# remote.net
KiCad netlist of a schematic drawn in EAGLE
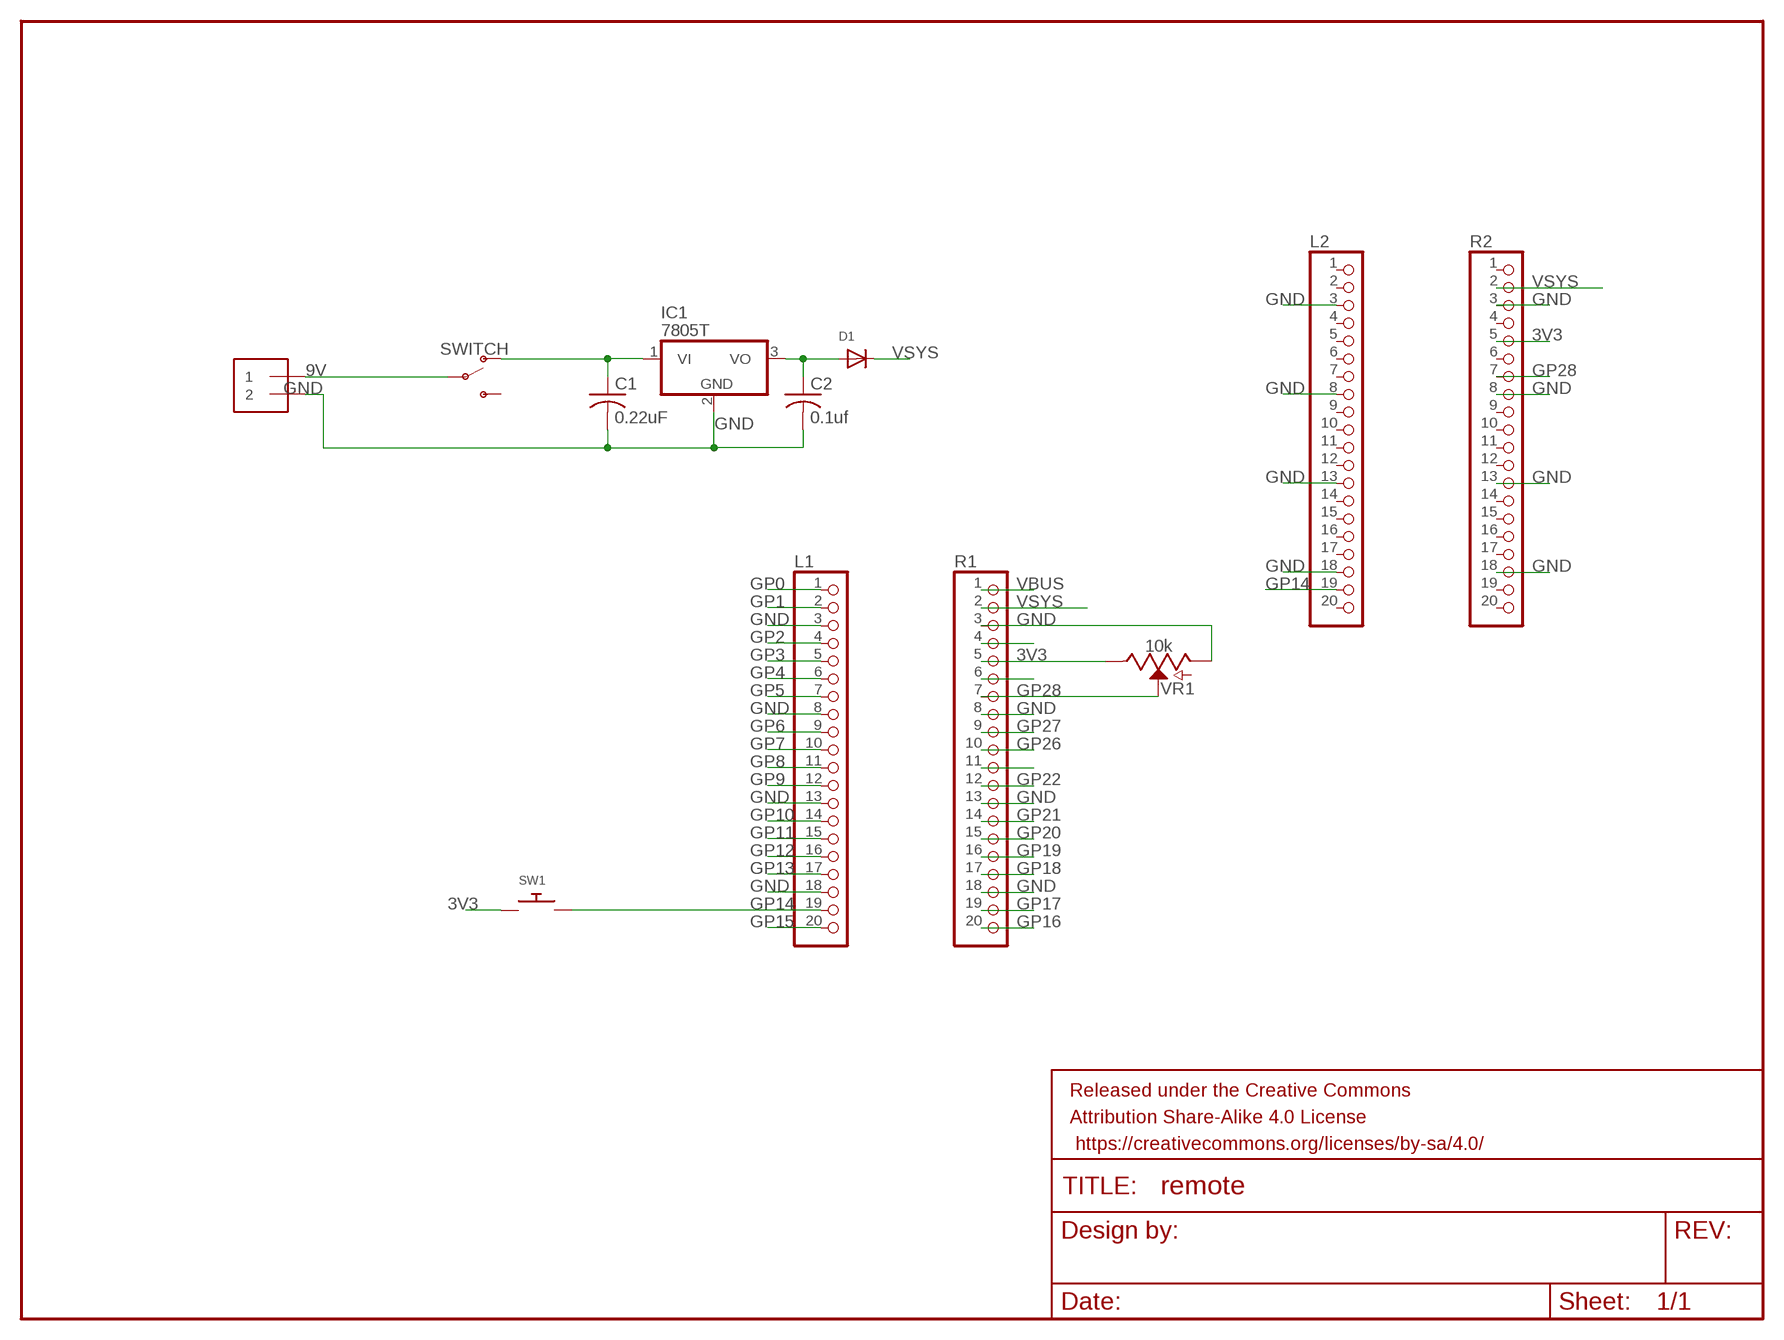
[diagram p0: schematic, sheet 1]

(export (version "E")
  (design (tool "Eeschema 10.0.6"))
  (components
    (comp (ref "9VBAT")
      (value "1X2-3.5MM")
      (footprint "eagle-import:1X2-3.5MM")
      (libsource (lib "eagle-import") (part "1X2-3.5MM"))
    )
    (comp (ref "C1")
      (value "0.22uF")
      (footprint "eagle-import:C050-025X075")
      (libsource (lib "eagle-import") (part "C-US050-025X075"))
    )
    (comp (ref "C2")
      (value "0.1uf")
      (footprint "eagle-import:C050-025X075")
      (libsource (lib "eagle-import") (part "C-US050-025X075"))
    )
    (comp (ref "D1")
      (value "DIODEDO-1N4148")
      (footprint "eagle-import:DO-1N4148")
      (libsource (lib "eagle-import") (part "DIODEDO-1N4148"))
    )
    (comp (ref "FRAME1")
      (value "FRAME-LETTER")
      (footprint "eagle-import:CREATIVE_COMMONS")
      (libsource (lib "eagle-import") (part "FRAME-LETTER"))
    )
    (comp (ref "IC1")
      (value "7805T")
      (footprint "eagle-import:TO220H")
      (libsource (lib "eagle-import") (part "78T05"))
    )
    (comp (ref "L1")
      (value "PINHD-1X20")
      (footprint "eagle-import:1X20")
      (libsource (lib "eagle-import") (part "PINHD-1X20"))
    )
    (comp (ref "L2")
      (value "PINHD-1X20")
      (footprint "eagle-import:1X20")
      (libsource (lib "eagle-import") (part "PINHD-1X20"))
    )
    (comp (ref "R1")
      (value "PINHD-1X20")
      (footprint "eagle-import:1X20")
      (libsource (lib "eagle-import") (part "PINHD-1X20"))
    )
    (comp (ref "R2")
      (value "PINHD-1X20")
      (footprint "eagle-import:1X20")
      (libsource (lib "eagle-import") (part "PINHD-1X20"))
    )
    (comp (ref "SW1")
      (value "SWITCH_PUSHBUTTONEVQ-PE")
      (footprint "eagle-import:TACT_PANA-EVQ")
      (libsource (lib "eagle-import") (part "SWITCH_PUSHBUTTONEVQ-PE"))
    )
    (comp (ref "SWITCH")
      (value "SWITCH-SPDT-PTH-11.6X4.0MM-LOCK")
      (footprint "eagle-import:SWITCH_SPDT_PTH_11.6X4.0MM_LOCK")
      (libsource (lib "eagle-import") (part "SWITCH-SPDT-PTH-11.6X4.0MM-LOCK"))
    )
    (comp (ref "VR1")
      (value "10k")
      (footprint "eagle-import:POT-PTH-ALPS")
      (libsource (lib "eagle-import") (part "POTENTIOMETER-PTH-9MM-1/20W-20%"))
    )
  )
  (nets
    (net (code "1") (name "/3V3") (class "Default")
      (node (ref "R1") (pin "5") (pinfunction "5_5") (pintype "passive"))
      (node (ref "R2") (pin "5") (pinfunction "5_5") (pintype "passive"))
      (node (ref "SW1") (pin "P$1") (pinfunction "P$1_P$1") (pintype "passive"))
      (node (ref "VR1") (pin "P$1") (pinfunction "E_P$1") (pintype "passive"))
    )
    (net (code "2") (name "/9V") (class "Default")
      (node (ref "9VBAT") (pin "1") (pinfunction "1_1") (pintype "passive"))
      (node (ref "SWITCH") (pin "2") (pinfunction "P_2") (pintype "passive"))
    )
    (net (code "3") (name "/GND") (class "Default")
      (node (ref "9VBAT") (pin "2") (pinfunction "2_2") (pintype "passive"))
      (node (ref "C1") (pin "2") (pinfunction "2_2") (pintype "passive"))
      (node (ref "C2") (pin "2") (pinfunction "2_2") (pintype "passive"))
      (node (ref "IC1") (pin "2") (pinfunction "GND_2") (pintype "passive"))
      (node (ref "L1") (pin "13") (pinfunction "13_13") (pintype "passive"))
      (node (ref "L1") (pin "18") (pinfunction "18_18") (pintype "passive"))
      (node (ref "L1") (pin "3") (pinfunction "3_3") (pintype "passive"))
      (node (ref "L1") (pin "8") (pinfunction "8_8") (pintype "passive"))
      (node (ref "L2") (pin "13") (pinfunction "13_13") (pintype "passive"))
      (node (ref "L2") (pin "18") (pinfunction "18_18") (pintype "passive"))
      (node (ref "L2") (pin "3") (pinfunction "3_3") (pintype "passive"))
      (node (ref "L2") (pin "8") (pinfunction "8_8") (pintype "passive"))
      (node (ref "R1") (pin "13") (pinfunction "13_13") (pintype "passive"))
      (node (ref "R1") (pin "18") (pinfunction "18_18") (pintype "passive"))
      (node (ref "R1") (pin "3") (pinfunction "3_3") (pintype "passive"))
      (node (ref "R1") (pin "8") (pinfunction "8_8") (pintype "passive"))
      (node (ref "R2") (pin "13") (pinfunction "13_13") (pintype "passive"))
      (node (ref "R2") (pin "18") (pinfunction "18_18") (pintype "passive"))
      (node (ref "R2") (pin "3") (pinfunction "3_3") (pintype "passive"))
      (node (ref "R2") (pin "8") (pinfunction "8_8") (pintype "passive"))
      (node (ref "VR1") (pin "P$3") (pinfunction "A_P$3") (pintype "passive"))
    )
    (net (code "4") (name "/GP0") (class "Default")
      (node (ref "L1") (pin "1") (pinfunction "1_1") (pintype "passive"))
    )
    (net (code "5") (name "/GP1") (class "Default")
      (node (ref "L1") (pin "2") (pinfunction "2_2") (pintype "passive"))
    )
    (net (code "6") (name "/GP2") (class "Default")
      (node (ref "L1") (pin "4") (pinfunction "4_4") (pintype "passive"))
    )
    (net (code "7") (name "/GP3") (class "Default")
      (node (ref "L1") (pin "5") (pinfunction "5_5") (pintype "passive"))
    )
    (net (code "8") (name "/GP4") (class "Default")
      (node (ref "L1") (pin "6") (pinfunction "6_6") (pintype "passive"))
    )
    (net (code "9") (name "/GP5") (class "Default")
      (node (ref "L1") (pin "7") (pinfunction "7_7") (pintype "passive"))
    )
    (net (code "10") (name "/GP6") (class "Default")
      (node (ref "L1") (pin "9") (pinfunction "9_9") (pintype "passive"))
    )
    (net (code "11") (name "/GP7") (class "Default")
      (node (ref "L1") (pin "10") (pinfunction "10_10") (pintype "passive"))
    )
    (net (code "12") (name "/GP8") (class "Default")
      (node (ref "L1") (pin "11") (pinfunction "11_11") (pintype "passive"))
    )
    (net (code "13") (name "/GP9") (class "Default")
      (node (ref "L1") (pin "12") (pinfunction "12_12") (pintype "passive"))
    )
    (net (code "14") (name "/GP10") (class "Default")
      (node (ref "L1") (pin "14") (pinfunction "14_14") (pintype "passive"))
    )
    (net (code "15") (name "/GP11") (class "Default")
      (node (ref "L1") (pin "15") (pinfunction "15_15") (pintype "passive"))
    )
    (net (code "16") (name "/GP12") (class "Default")
      (node (ref "L1") (pin "16") (pinfunction "16_16") (pintype "passive"))
    )
    (net (code "17") (name "/GP13") (class "Default")
      (node (ref "L1") (pin "17") (pinfunction "17_17") (pintype "passive"))
    )
    (net (code "18") (name "/GP14") (class "Default")
      (node (ref "L1") (pin "19") (pinfunction "19_19") (pintype "passive"))
      (node (ref "L2") (pin "19") (pinfunction "19_19") (pintype "passive"))
      (node (ref "SW1") (pin "P$2") (pinfunction "P$2_P$2") (pintype "passive"))
    )
    (net (code "19") (name "/GP15") (class "Default")
      (node (ref "L1") (pin "20") (pinfunction "20_20") (pintype "passive"))
    )
    (net (code "20") (name "/GP16") (class "Default")
      (node (ref "R1") (pin "20") (pinfunction "20_20") (pintype "passive"))
    )
    (net (code "21") (name "/GP17") (class "Default")
      (node (ref "R1") (pin "19") (pinfunction "19_19") (pintype "passive"))
    )
    (net (code "22") (name "/GP18") (class "Default")
      (node (ref "R1") (pin "17") (pinfunction "17_17") (pintype "passive"))
    )
    (net (code "23") (name "/GP19") (class "Default")
      (node (ref "R1") (pin "16") (pinfunction "16_16") (pintype "passive"))
    )
    (net (code "24") (name "/GP20") (class "Default")
      (node (ref "R1") (pin "15") (pinfunction "15_15") (pintype "passive"))
    )
    (net (code "25") (name "/GP21") (class "Default")
      (node (ref "R1") (pin "14") (pinfunction "14_14") (pintype "passive"))
    )
    (net (code "26") (name "/GP22") (class "Default")
      (node (ref "R1") (pin "12") (pinfunction "12_12") (pintype "passive"))
    )
    (net (code "27") (name "/GP26") (class "Default")
      (node (ref "R1") (pin "10") (pinfunction "10_10") (pintype "passive"))
    )
    (net (code "28") (name "/GP27") (class "Default")
      (node (ref "R1") (pin "9") (pinfunction "9_9") (pintype "passive"))
    )
    (net (code "29") (name "/GP28") (class "Default")
      (node (ref "R1") (pin "7") (pinfunction "7_7") (pintype "passive"))
      (node (ref "R2") (pin "7") (pinfunction "7_7") (pintype "passive"))
      (node (ref "VR1") (pin "P$2") (pinfunction "S_P$2") (pintype "passive"))
    )
    (net (code "30") (name "/VBUS") (class "Default")
      (node (ref "R1") (pin "1") (pinfunction "1_1") (pintype "passive"))
    )
    (net (code "31") (name "/VSYS") (class "Default")
      (node (ref "D1") (pin "C") (pinfunction "C_C") (pintype "passive"))
      (node (ref "R1") (pin "2") (pinfunction "2_2") (pintype "passive"))
      (node (ref "R2") (pin "2") (pinfunction "2_2") (pintype "passive"))
    )
    (net (code "32") (name "Net-(IC1-VI)") (class "Default")
      (node (ref "C1") (pin "1") (pinfunction "1_1") (pintype "passive"))
      (node (ref "IC1") (pin "1") (pinfunction "VI_1") (pintype "input"))
      (node (ref "SWITCH") (pin "1") (pinfunction "O_1") (pintype "passive"))
    )
    (net (code "33") (name "Net-(IC1-VO)") (class "Default")
      (node (ref "C2") (pin "1") (pinfunction "1_1") (pintype "passive"))
      (node (ref "D1") (pin "A") (pinfunction "A_A") (pintype "passive"))
      (node (ref "IC1") (pin "3") (pinfunction "VO_3") (pintype "passive"))
    )
    (net (code "34") (name "unconnected-(L2-Pad1)") (class "Default")
      (node (ref "L2") (pin "1") (pinfunction "1_1") (pintype "passive"))
    )
    (net (code "35") (name "unconnected-(L2-Pad2)") (class "Default")
      (node (ref "L2") (pin "2") (pinfunction "2_2") (pintype "passive"))
    )
    (net (code "36") (name "unconnected-(L2-Pad4)") (class "Default")
      (node (ref "L2") (pin "4") (pinfunction "4_4") (pintype "passive"))
    )
    (net (code "37") (name "unconnected-(L2-Pad5)") (class "Default")
      (node (ref "L2") (pin "5") (pinfunction "5_5") (pintype "passive"))
    )
    (net (code "38") (name "unconnected-(L2-Pad6)") (class "Default")
      (node (ref "L2") (pin "6") (pinfunction "6_6") (pintype "passive"))
    )
    (net (code "39") (name "unconnected-(L2-Pad7)") (class "Default")
      (node (ref "L2") (pin "7") (pinfunction "7_7") (pintype "passive"))
    )
    (net (code "40") (name "unconnected-(L2-Pad9)") (class "Default")
      (node (ref "L2") (pin "9") (pinfunction "9_9") (pintype "passive"))
    )
    (net (code "41") (name "unconnected-(L2-Pad10)") (class "Default")
      (node (ref "L2") (pin "10") (pinfunction "10_10") (pintype "passive"))
    )
    (net (code "42") (name "unconnected-(L2-Pad11)") (class "Default")
      (node (ref "L2") (pin "11") (pinfunction "11_11") (pintype "passive"))
    )
    (net (code "43") (name "unconnected-(L2-Pad12)") (class "Default")
      (node (ref "L2") (pin "12") (pinfunction "12_12") (pintype "passive"))
    )
    (net (code "44") (name "unconnected-(L2-Pad14)") (class "Default")
      (node (ref "L2") (pin "14") (pinfunction "14_14") (pintype "passive"))
    )
    (net (code "45") (name "unconnected-(L2-Pad15)") (class "Default")
      (node (ref "L2") (pin "15") (pinfunction "15_15") (pintype "passive"))
    )
    (net (code "46") (name "unconnected-(L2-Pad16)") (class "Default")
      (node (ref "L2") (pin "16") (pinfunction "16_16") (pintype "passive"))
    )
    (net (code "47") (name "unconnected-(L2-Pad17)") (class "Default")
      (node (ref "L2") (pin "17") (pinfunction "17_17") (pintype "passive"))
    )
    (net (code "48") (name "unconnected-(L2-Pad20)") (class "Default")
      (node (ref "L2") (pin "20") (pinfunction "20_20") (pintype "passive"))
    )
    (net (code "49") (name "unconnected-(R1-Pad4)") (class "Default")
      (node (ref "R1") (pin "4") (pinfunction "4_4") (pintype "passive"))
    )
    (net (code "50") (name "unconnected-(R1-Pad6)") (class "Default")
      (node (ref "R1") (pin "6") (pinfunction "6_6") (pintype "passive"))
    )
    (net (code "51") (name "unconnected-(R1-Pad11)") (class "Default")
      (node (ref "R1") (pin "11") (pinfunction "11_11") (pintype "passive"))
    )
    (net (code "52") (name "unconnected-(R2-Pad1)") (class "Default")
      (node (ref "R2") (pin "1") (pinfunction "1_1") (pintype "passive"))
    )
    (net (code "53") (name "unconnected-(R2-Pad4)") (class "Default")
      (node (ref "R2") (pin "4") (pinfunction "4_4") (pintype "passive"))
    )
    (net (code "54") (name "unconnected-(R2-Pad6)") (class "Default")
      (node (ref "R2") (pin "6") (pinfunction "6_6") (pintype "passive"))
    )
    (net (code "55") (name "unconnected-(R2-Pad9)") (class "Default")
      (node (ref "R2") (pin "9") (pinfunction "9_9") (pintype "passive"))
    )
    (net (code "56") (name "unconnected-(R2-Pad10)") (class "Default")
      (node (ref "R2") (pin "10") (pinfunction "10_10") (pintype "passive"))
    )
    (net (code "57") (name "unconnected-(R2-Pad11)") (class "Default")
      (node (ref "R2") (pin "11") (pinfunction "11_11") (pintype "passive"))
    )
    (net (code "58") (name "unconnected-(R2-Pad12)") (class "Default")
      (node (ref "R2") (pin "12") (pinfunction "12_12") (pintype "passive"))
    )
    (net (code "59") (name "unconnected-(R2-Pad14)") (class "Default")
      (node (ref "R2") (pin "14") (pinfunction "14_14") (pintype "passive"))
    )
    (net (code "60") (name "unconnected-(R2-Pad15)") (class "Default")
      (node (ref "R2") (pin "15") (pinfunction "15_15") (pintype "passive"))
    )
    (net (code "61") (name "unconnected-(R2-Pad16)") (class "Default")
      (node (ref "R2") (pin "16") (pinfunction "16_16") (pintype "passive"))
    )
    (net (code "62") (name "unconnected-(R2-Pad17)") (class "Default")
      (node (ref "R2") (pin "17") (pinfunction "17_17") (pintype "passive"))
    )
    (net (code "63") (name "unconnected-(R2-Pad19)") (class "Default")
      (node (ref "R2") (pin "19") (pinfunction "19_19") (pintype "passive"))
    )
    (net (code "64") (name "unconnected-(R2-Pad20)") (class "Default")
      (node (ref "R2") (pin "20") (pinfunction "20_20") (pintype "passive"))
    )
    (net (code "65") (name "unconnected-(SWITCH-S-Pad3)") (class "Default")
      (node (ref "SWITCH") (pin "3") (pinfunction "S_3") (pintype "passive"))
    )
  )
)
